# controller.net
KiCad netlist of a schematic drawn in EAGLE
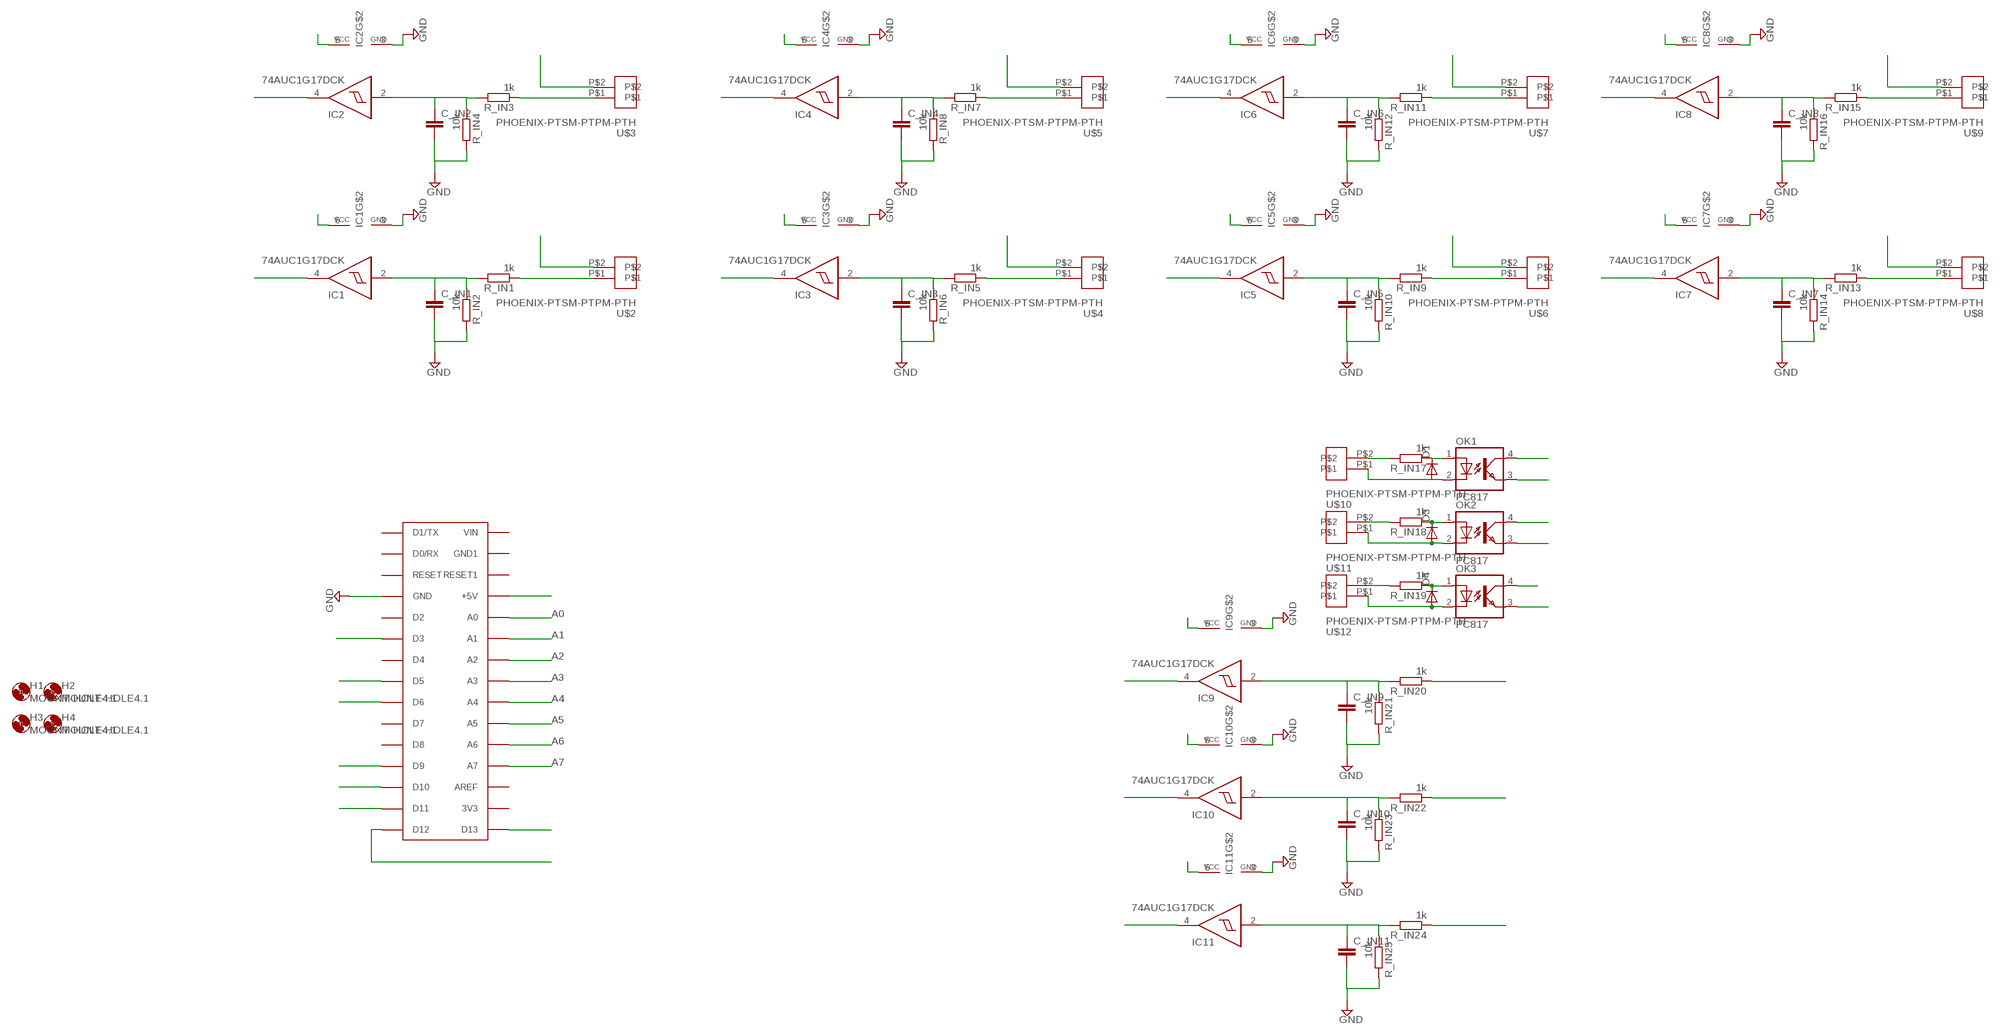
[diagram p0: schematic, sheet 1]

(export (version "E")
  (design (tool "Eeschema 10.0.6"))
  (components
    (comp (ref "C_IN1")
      (value "C-EUC0805")
      (footprint "eagle-import:C0805")
      (libsource (lib "eagle-import") (part "C-EUC0805"))
    )
    (comp (ref "C_IN2")
      (value "C-EUC0805")
      (footprint "eagle-import:C0805")
      (libsource (lib "eagle-import") (part "C-EUC0805"))
    )
    (comp (ref "C_IN3")
      (value "C-EUC0805")
      (footprint "eagle-import:C0805")
      (libsource (lib "eagle-import") (part "C-EUC0805"))
    )
    (comp (ref "C_IN4")
      (value "C-EUC0805")
      (footprint "eagle-import:C0805")
      (libsource (lib "eagle-import") (part "C-EUC0805"))
    )
    (comp (ref "C_IN5")
      (value "C-EUC0805")
      (footprint "eagle-import:C0805")
      (libsource (lib "eagle-import") (part "C-EUC0805"))
    )
    (comp (ref "C_IN6")
      (value "C-EUC0805")
      (footprint "eagle-import:C0805")
      (libsource (lib "eagle-import") (part "C-EUC0805"))
    )
    (comp (ref "C_IN7")
      (value "C-EUC0805")
      (footprint "eagle-import:C0805")
      (libsource (lib "eagle-import") (part "C-EUC0805"))
    )
    (comp (ref "C_IN8")
      (value "C-EUC0805")
      (footprint "eagle-import:C0805")
      (libsource (lib "eagle-import") (part "C-EUC0805"))
    )
    (comp (ref "C_IN9")
      (value "C-EUC0805")
      (footprint "eagle-import:C0805")
      (libsource (lib "eagle-import") (part "C-EUC0805"))
    )
    (comp (ref "C_IN10")
      (value "C-EUC0805")
      (footprint "eagle-import:C0805")
      (libsource (lib "eagle-import") (part "C-EUC0805"))
    )
    (comp (ref "C_IN11")
      (value "C-EUC0805")
      (footprint "eagle-import:C0805")
      (libsource (lib "eagle-import") (part "C-EUC0805"))
    )
    (comp (ref "D1")
      (value "DIODE-DO-214AC")
      (footprint "eagle-import:DO-214AC")
      (libsource (lib "eagle-import") (part "DIODE-DO-214AC"))
    )
    (comp (ref "D3")
      (value "DIODE-DO-214AC")
      (footprint "eagle-import:DO-214AC")
      (libsource (lib "eagle-import") (part "DIODE-DO-214AC"))
    )
    (comp (ref "D4")
      (value "DIODE-DO-214AC")
      (footprint "eagle-import:DO-214AC")
      (libsource (lib "eagle-import") (part "DIODE-DO-214AC"))
    )
    (comp (ref "H1")
      (value "MOUNT-HOLE4.1")
      (footprint "eagle-import:4,1")
      (libsource (lib "eagle-import") (part "MOUNT-HOLE4.1"))
    )
    (comp (ref "H2")
      (value "MOUNT-HOLE4.1")
      (footprint "eagle-import:4,1")
      (libsource (lib "eagle-import") (part "MOUNT-HOLE4.1"))
    )
    (comp (ref "H3")
      (value "MOUNT-HOLE4.1")
      (footprint "eagle-import:4,1")
      (libsource (lib "eagle-import") (part "MOUNT-HOLE4.1"))
    )
    (comp (ref "H4")
      (value "MOUNT-HOLE4.1")
      (footprint "eagle-import:4,1")
      (libsource (lib "eagle-import") (part "MOUNT-HOLE4.1"))
    )
    (comp (ref "IC1")
      (value "74AUC1G17DCK")
      (footprint "eagle-import:SC70-5")
      (libsource (lib "eagle-import") (part "741G17DCKAUC"))
    )
    (comp (ref "IC2")
      (value "74AUC1G17DCK")
      (footprint "eagle-import:SC70-5")
      (libsource (lib "eagle-import") (part "741G17DCKAUC"))
    )
    (comp (ref "IC3")
      (value "74AUC1G17DCK")
      (footprint "eagle-import:SC70-5")
      (libsource (lib "eagle-import") (part "741G17DCKAUC"))
    )
    (comp (ref "IC4")
      (value "74AUC1G17DCK")
      (footprint "eagle-import:SC70-5")
      (libsource (lib "eagle-import") (part "741G17DCKAUC"))
    )
    (comp (ref "IC5")
      (value "74AUC1G17DCK")
      (footprint "eagle-import:SC70-5")
      (libsource (lib "eagle-import") (part "741G17DCKAUC"))
    )
    (comp (ref "IC6")
      (value "74AUC1G17DCK")
      (footprint "eagle-import:SC70-5")
      (libsource (lib "eagle-import") (part "741G17DCKAUC"))
    )
    (comp (ref "IC7")
      (value "74AUC1G17DCK")
      (footprint "eagle-import:SC70-5")
      (libsource (lib "eagle-import") (part "741G17DCKAUC"))
    )
    (comp (ref "IC8")
      (value "74AUC1G17DCK")
      (footprint "eagle-import:SC70-5")
      (libsource (lib "eagle-import") (part "741G17DCKAUC"))
    )
    (comp (ref "IC9")
      (value "74AUC1G17DCK")
      (footprint "eagle-import:SC70-5")
      (libsource (lib "eagle-import") (part "741G17DCKAUC"))
    )
    (comp (ref "IC10")
      (value "74AUC1G17DCK")
      (footprint "eagle-import:SC70-5")
      (libsource (lib "eagle-import") (part "741G17DCKAUC"))
    )
    (comp (ref "IC11")
      (value "74AUC1G17DCK")
      (footprint "eagle-import:SC70-5")
      (libsource (lib "eagle-import") (part "741G17DCKAUC"))
    )
    (comp (ref "OK1")
      (value "PC817")
      (footprint "eagle-import:DIL04")
      (fields (field (name "MPN") "PC817X4J000F"))
      (libsource (lib "eagle-import") (part "PC817"))
    )
    (comp (ref "OK2")
      (value "PC817")
      (footprint "eagle-import:DIL04")
      (fields (field (name "MPN") "PC817X4J000F"))
      (libsource (lib "eagle-import") (part "PC817"))
    )
    (comp (ref "OK3")
      (value "PC817")
      (footprint "eagle-import:DIL04")
      (fields
        (field (name "MPN") "PC817X4J000F")
        (field (name "MPN_1") "PC817X4J000F")
        (field (name "OC_FARNELL") "9707727")
        (field (name "OC_NEWARK") "97K7059")
      )
      (libsource (lib "eagle-import") (part "PC817"))
    )
    (comp (ref "R_IN1")
      (value "1k")
      (footprint "eagle-import:M0805")
      (libsource (lib "eagle-import") (part "R-EU_M0805"))
    )
    (comp (ref "R_IN2")
      (value "10k")
      (footprint "eagle-import:M0805")
      (libsource (lib "eagle-import") (part "R-EU_M0805"))
    )
    (comp (ref "R_IN3")
      (value "1k")
      (footprint "eagle-import:M0805")
      (libsource (lib "eagle-import") (part "R-EU_M0805"))
    )
    (comp (ref "R_IN4")
      (value "10k")
      (footprint "eagle-import:M0805")
      (libsource (lib "eagle-import") (part "R-EU_M0805"))
    )
    (comp (ref "R_IN5")
      (value "1k")
      (footprint "eagle-import:M0805")
      (libsource (lib "eagle-import") (part "R-EU_M0805"))
    )
    (comp (ref "R_IN6")
      (value "10k")
      (footprint "eagle-import:M0805")
      (libsource (lib "eagle-import") (part "R-EU_M0805"))
    )
    (comp (ref "R_IN7")
      (value "1k")
      (footprint "eagle-import:M0805")
      (libsource (lib "eagle-import") (part "R-EU_M0805"))
    )
    (comp (ref "R_IN8")
      (value "10k")
      (footprint "eagle-import:M0805")
      (libsource (lib "eagle-import") (part "R-EU_M0805"))
    )
    (comp (ref "R_IN9")
      (value "1k")
      (footprint "eagle-import:M0805")
      (libsource (lib "eagle-import") (part "R-EU_M0805"))
    )
    (comp (ref "R_IN10")
      (value "10k")
      (footprint "eagle-import:M0805")
      (libsource (lib "eagle-import") (part "R-EU_M0805"))
    )
    (comp (ref "R_IN11")
      (value "1k")
      (footprint "eagle-import:M0805")
      (libsource (lib "eagle-import") (part "R-EU_M0805"))
    )
    (comp (ref "R_IN12")
      (value "10k")
      (footprint "eagle-import:M0805")
      (libsource (lib "eagle-import") (part "R-EU_M0805"))
    )
    (comp (ref "R_IN13")
      (value "1k")
      (footprint "eagle-import:M0805")
      (libsource (lib "eagle-import") (part "R-EU_M0805"))
    )
    (comp (ref "R_IN14")
      (value "10k")
      (footprint "eagle-import:M0805")
      (libsource (lib "eagle-import") (part "R-EU_M0805"))
    )
    (comp (ref "R_IN15")
      (value "1k")
      (footprint "eagle-import:M0805")
      (libsource (lib "eagle-import") (part "R-EU_M0805"))
    )
    (comp (ref "R_IN16")
      (value "10k")
      (footprint "eagle-import:M0805")
      (libsource (lib "eagle-import") (part "R-EU_M0805"))
    )
    (comp (ref "R_IN17")
      (value "1k")
      (footprint "eagle-import:M1206")
      (libsource (lib "eagle-import") (part "R-EU_M1206"))
    )
    (comp (ref "R_IN18")
      (value "1k")
      (footprint "eagle-import:M1206")
      (libsource (lib "eagle-import") (part "R-EU_M1206"))
    )
    (comp (ref "R_IN19")
      (value "1k")
      (footprint "eagle-import:M1206")
      (libsource (lib "eagle-import") (part "R-EU_M1206"))
    )
    (comp (ref "R_IN20")
      (value "1k")
      (footprint "eagle-import:M0805")
      (libsource (lib "eagle-import") (part "R-EU_M0805"))
    )
    (comp (ref "R_IN21")
      (value "10k")
      (footprint "eagle-import:M0805")
      (libsource (lib "eagle-import") (part "R-EU_M0805"))
    )
    (comp (ref "R_IN22")
      (value "1k")
      (footprint "eagle-import:M0805")
      (libsource (lib "eagle-import") (part "R-EU_M0805"))
    )
    (comp (ref "R_IN23")
      (value "10k")
      (footprint "eagle-import:M0805")
      (libsource (lib "eagle-import") (part "R-EU_M0805"))
    )
    (comp (ref "R_IN24")
      (value "1k")
      (footprint "eagle-import:M0805")
      (libsource (lib "eagle-import") (part "R-EU_M0805"))
    )
    (comp (ref "R_IN25")
      (value "10k")
      (footprint "eagle-import:M0805")
      (libsource (lib "eagle-import") (part "R-EU_M0805"))
    )
    (comp (ref "U$1")
      (value "ARDUINONANO")
      (footprint "eagle-import:PDIP-32")
      (libsource (lib "eagle-import") (part "ARDUINONANO"))
    )
    (comp (ref "U$2")
      (value "PHOENIX-PTSM-PTPM-PTH")
      (footprint "eagle-import:PTSM-PTH-2.5MM-2")
      (libsource (lib "eagle-import") (part "PHOENIX-PTSM-PTPM-PTH"))
    )
    (comp (ref "U$3")
      (value "PHOENIX-PTSM-PTPM-PTH")
      (footprint "eagle-import:PTSM-PTH-2.5MM-2")
      (libsource (lib "eagle-import") (part "PHOENIX-PTSM-PTPM-PTH"))
    )
    (comp (ref "U$4")
      (value "PHOENIX-PTSM-PTPM-PTH")
      (footprint "eagle-import:PTSM-PTH-2.5MM-2")
      (libsource (lib "eagle-import") (part "PHOENIX-PTSM-PTPM-PTH"))
    )
    (comp (ref "U$5")
      (value "PHOENIX-PTSM-PTPM-PTH")
      (footprint "eagle-import:PTSM-PTH-2.5MM-2")
      (libsource (lib "eagle-import") (part "PHOENIX-PTSM-PTPM-PTH"))
    )
    (comp (ref "U$6")
      (value "PHOENIX-PTSM-PTPM-PTH")
      (footprint "eagle-import:PTSM-PTH-2.5MM-2")
      (libsource (lib "eagle-import") (part "PHOENIX-PTSM-PTPM-PTH"))
    )
    (comp (ref "U$7")
      (value "PHOENIX-PTSM-PTPM-PTH")
      (footprint "eagle-import:PTSM-PTH-2.5MM-2")
      (libsource (lib "eagle-import") (part "PHOENIX-PTSM-PTPM-PTH"))
    )
    (comp (ref "U$8")
      (value "PHOENIX-PTSM-PTPM-PTH")
      (footprint "eagle-import:PTSM-PTH-2.5MM-2")
      (libsource (lib "eagle-import") (part "PHOENIX-PTSM-PTPM-PTH"))
    )
    (comp (ref "U$9")
      (value "PHOENIX-PTSM-PTPM-PTH")
      (footprint "eagle-import:PTSM-PTH-2.5MM-2")
      (libsource (lib "eagle-import") (part "PHOENIX-PTSM-PTPM-PTH"))
    )
    (comp (ref "U$10")
      (value "PHOENIX-PTSM-PTPM-PTH")
      (footprint "eagle-import:PTSM-PTH-2.5MM-2")
      (libsource (lib "eagle-import") (part "PHOENIX-PTSM-PTPM-PTH"))
    )
    (comp (ref "U$11")
      (value "PHOENIX-PTSM-PTPM-PTH")
      (footprint "eagle-import:PTSM-PTH-2.5MM-2")
      (libsource (lib "eagle-import") (part "PHOENIX-PTSM-PTPM-PTH"))
    )
    (comp (ref "U$12")
      (value "PHOENIX-PTSM-PTPM-PTH")
      (footprint "eagle-import:PTSM-PTH-2.5MM-2")
      (libsource (lib "eagle-import") (part "PHOENIX-PTSM-PTPM-PTH"))
    )
  )
  (nets
    (net (code "1") (name "/+5V") (class "Default")
      (node (ref "IC1") (pin "5") (pinfunction "VCC_5") (pintype "power_in"))
      (node (ref "IC2") (pin "5") (pinfunction "VCC_5") (pintype "power_in"))
      (node (ref "IC3") (pin "5") (pinfunction "VCC_5") (pintype "power_in"))
      (node (ref "IC4") (pin "5") (pinfunction "VCC_5") (pintype "power_in"))
      (node (ref "IC5") (pin "5") (pinfunction "VCC_5") (pintype "power_in"))
      (node (ref "IC6") (pin "5") (pinfunction "VCC_5") (pintype "power_in"))
      (node (ref "IC7") (pin "5") (pinfunction "VCC_5") (pintype "power_in"))
      (node (ref "IC8") (pin "5") (pinfunction "VCC_5") (pintype "power_in"))
      (node (ref "OK1") (pin "4") (pinfunction "COL_4") (pintype "passive"))
      (node (ref "OK2") (pin "4") (pinfunction "COL_4") (pintype "passive"))
      (node (ref "OK3") (pin "4") (pinfunction "COL_4") (pintype "passive"))
      (node (ref "U$1") (pin "+5V") (pinfunction "+5V_+5V") (pintype "bidirectional"))
      (node (ref "U$2") (pin "P$2") (pinfunction "P$2_P$2") (pintype "bidirectional"))
      (node (ref "U$3") (pin "P$2") (pinfunction "P$2_P$2") (pintype "bidirectional"))
      (node (ref "U$4") (pin "P$2") (pinfunction "P$2_P$2") (pintype "bidirectional"))
      (node (ref "U$5") (pin "P$2") (pinfunction "P$2_P$2") (pintype "bidirectional"))
      (node (ref "U$6") (pin "P$2") (pinfunction "P$2_P$2") (pintype "bidirectional"))
      (node (ref "U$7") (pin "P$2") (pinfunction "P$2_P$2") (pintype "bidirectional"))
      (node (ref "U$8") (pin "P$2") (pinfunction "P$2_P$2") (pintype "bidirectional"))
      (node (ref "U$9") (pin "P$2") (pinfunction "P$2_P$2") (pintype "bidirectional"))
    )
    (net (code "2") (name "/A0") (class "Default")
      (node (ref "IC1") (pin "4") (pinfunction "O_4") (pintype "output"))
      (node (ref "U$1") (pin "A0") (pinfunction "A0_A0") (pintype "bidirectional"))
    )
    (net (code "3") (name "/A1") (class "Default")
      (node (ref "IC2") (pin "4") (pinfunction "O_4") (pintype "output"))
      (node (ref "U$1") (pin "A1") (pinfunction "A1_A1") (pintype "bidirectional"))
    )
    (net (code "4") (name "/A2") (class "Default")
      (node (ref "IC3") (pin "4") (pinfunction "O_4") (pintype "output"))
      (node (ref "U$1") (pin "A2") (pinfunction "A2_A2") (pintype "bidirectional"))
    )
    (net (code "5") (name "/A3") (class "Default")
      (node (ref "IC4") (pin "4") (pinfunction "O_4") (pintype "output"))
      (node (ref "U$1") (pin "A3") (pinfunction "A3_A3") (pintype "bidirectional"))
    )
    (net (code "6") (name "/A4") (class "Default")
      (node (ref "IC5") (pin "4") (pinfunction "O_4") (pintype "output"))
      (node (ref "U$1") (pin "A4") (pinfunction "A4_A4") (pintype "bidirectional"))
    )
    (net (code "7") (name "/A5") (class "Default")
      (node (ref "IC6") (pin "4") (pinfunction "O_4") (pintype "output"))
      (node (ref "U$1") (pin "A5") (pinfunction "A5_A5") (pintype "bidirectional"))
    )
    (net (code "8") (name "/A6") (class "Default")
      (node (ref "IC7") (pin "4") (pinfunction "O_4") (pintype "output"))
      (node (ref "U$1") (pin "A6") (pinfunction "A6_A6") (pintype "bidirectional"))
    )
    (net (code "9") (name "/A7") (class "Default")
      (node (ref "IC8") (pin "4") (pinfunction "O_4") (pintype "output"))
      (node (ref "U$1") (pin "A7") (pinfunction "A7_A7") (pintype "bidirectional"))
    )
    (net (code "10") (name "/N$21") (class "Default")
      (node (ref "OK1") (pin "3") (pinfunction "EMIT_3") (pintype "passive"))
      (node (ref "R_IN20") (pin "1") (pinfunction "1_1") (pintype "passive"))
    )
    (net (code "11") (name "/N$22") (class "Default")
      (node (ref "OK2") (pin "3") (pinfunction "EMIT_3") (pintype "passive"))
      (node (ref "R_IN22") (pin "1") (pinfunction "1_1") (pintype "passive"))
    )
    (net (code "12") (name "/N$23") (class "Default")
      (node (ref "OK3") (pin "3") (pinfunction "EMIT_3") (pintype "passive"))
      (node (ref "R_IN24") (pin "1") (pinfunction "1_1") (pintype "passive"))
    )
    (net (code "13") (name "GND") (class "Default")
      (node (ref "C_IN1") (pin "2") (pinfunction "2_2") (pintype "passive"))
      (node (ref "C_IN10") (pin "2") (pinfunction "2_2") (pintype "passive"))
      (node (ref "C_IN11") (pin "2") (pinfunction "2_2") (pintype "passive"))
      (node (ref "C_IN2") (pin "2") (pinfunction "2_2") (pintype "passive"))
      (node (ref "C_IN3") (pin "2") (pinfunction "2_2") (pintype "passive"))
      (node (ref "C_IN4") (pin "2") (pinfunction "2_2") (pintype "passive"))
      (node (ref "C_IN5") (pin "2") (pinfunction "2_2") (pintype "passive"))
      (node (ref "C_IN6") (pin "2") (pinfunction "2_2") (pintype "passive"))
      (node (ref "C_IN7") (pin "2") (pinfunction "2_2") (pintype "passive"))
      (node (ref "C_IN8") (pin "2") (pinfunction "2_2") (pintype "passive"))
      (node (ref "C_IN9") (pin "2") (pinfunction "2_2") (pintype "passive"))
      (node (ref "IC1") (pin "3") (pinfunction "GND_3") (pintype "power_in"))
      (node (ref "IC10") (pin "3") (pinfunction "GND_3") (pintype "power_in"))
      (node (ref "IC11") (pin "3") (pinfunction "GND_3") (pintype "power_in"))
      (node (ref "IC2") (pin "3") (pinfunction "GND_3") (pintype "power_in"))
      (node (ref "IC3") (pin "3") (pinfunction "GND_3") (pintype "power_in"))
      (node (ref "IC4") (pin "3") (pinfunction "GND_3") (pintype "power_in"))
      (node (ref "IC5") (pin "3") (pinfunction "GND_3") (pintype "power_in"))
      (node (ref "IC6") (pin "3") (pinfunction "GND_3") (pintype "power_in"))
      (node (ref "IC7") (pin "3") (pinfunction "GND_3") (pintype "power_in"))
      (node (ref "IC8") (pin "3") (pinfunction "GND_3") (pintype "power_in"))
      (node (ref "IC9") (pin "3") (pinfunction "GND_3") (pintype "power_in"))
      (node (ref "R_IN10") (pin "2") (pinfunction "2_2") (pintype "passive"))
      (node (ref "R_IN12") (pin "2") (pinfunction "2_2") (pintype "passive"))
      (node (ref "R_IN14") (pin "2") (pinfunction "2_2") (pintype "passive"))
      (node (ref "R_IN16") (pin "2") (pinfunction "2_2") (pintype "passive"))
      (node (ref "R_IN2") (pin "2") (pinfunction "2_2") (pintype "passive"))
      (node (ref "R_IN21") (pin "2") (pinfunction "2_2") (pintype "passive"))
      (node (ref "R_IN23") (pin "2") (pinfunction "2_2") (pintype "passive"))
      (node (ref "R_IN25") (pin "2") (pinfunction "2_2") (pintype "passive"))
      (node (ref "R_IN4") (pin "2") (pinfunction "2_2") (pintype "passive"))
      (node (ref "R_IN6") (pin "2") (pinfunction "2_2") (pintype "passive"))
      (node (ref "R_IN8") (pin "2") (pinfunction "2_2") (pintype "passive"))
      (node (ref "U$1") (pin "GND") (pinfunction "GND_GND") (pintype "bidirectional"))
    )
    (net (code "14") (name "Net-(IC1A-I)") (class "Default")
      (node (ref "C_IN1") (pin "1") (pinfunction "1_1") (pintype "passive"))
      (node (ref "IC1") (pin "2") (pinfunction "I_2") (pintype "input"))
      (node (ref "R_IN1") (pin "2") (pinfunction "2_2") (pintype "passive"))
      (node (ref "R_IN2") (pin "1") (pinfunction "1_1") (pintype "passive"))
    )
    (net (code "15") (name "Net-(IC2A-I)") (class "Default")
      (node (ref "C_IN2") (pin "1") (pinfunction "1_1") (pintype "passive"))
      (node (ref "IC2") (pin "2") (pinfunction "I_2") (pintype "input"))
      (node (ref "R_IN3") (pin "2") (pinfunction "2_2") (pintype "passive"))
      (node (ref "R_IN4") (pin "1") (pinfunction "1_1") (pintype "passive"))
    )
    (net (code "16") (name "Net-(IC3A-I)") (class "Default")
      (node (ref "C_IN3") (pin "1") (pinfunction "1_1") (pintype "passive"))
      (node (ref "IC3") (pin "2") (pinfunction "I_2") (pintype "input"))
      (node (ref "R_IN5") (pin "2") (pinfunction "2_2") (pintype "passive"))
      (node (ref "R_IN6") (pin "1") (pinfunction "1_1") (pintype "passive"))
    )
    (net (code "17") (name "Net-(IC4A-I)") (class "Default")
      (node (ref "C_IN4") (pin "1") (pinfunction "1_1") (pintype "passive"))
      (node (ref "IC4") (pin "2") (pinfunction "I_2") (pintype "input"))
      (node (ref "R_IN7") (pin "2") (pinfunction "2_2") (pintype "passive"))
      (node (ref "R_IN8") (pin "1") (pinfunction "1_1") (pintype "passive"))
    )
    (net (code "18") (name "Net-(IC5A-I)") (class "Default")
      (node (ref "C_IN5") (pin "1") (pinfunction "1_1") (pintype "passive"))
      (node (ref "IC5") (pin "2") (pinfunction "I_2") (pintype "input"))
      (node (ref "R_IN10") (pin "1") (pinfunction "1_1") (pintype "passive"))
      (node (ref "R_IN9") (pin "2") (pinfunction "2_2") (pintype "passive"))
    )
    (net (code "19") (name "Net-(IC6A-I)") (class "Default")
      (node (ref "C_IN6") (pin "1") (pinfunction "1_1") (pintype "passive"))
      (node (ref "IC6") (pin "2") (pinfunction "I_2") (pintype "input"))
      (node (ref "R_IN11") (pin "2") (pinfunction "2_2") (pintype "passive"))
      (node (ref "R_IN12") (pin "1") (pinfunction "1_1") (pintype "passive"))
    )
    (net (code "20") (name "Net-(IC7A-I)") (class "Default")
      (node (ref "C_IN7") (pin "1") (pinfunction "1_1") (pintype "passive"))
      (node (ref "IC7") (pin "2") (pinfunction "I_2") (pintype "input"))
      (node (ref "R_IN13") (pin "2") (pinfunction "2_2") (pintype "passive"))
      (node (ref "R_IN14") (pin "1") (pinfunction "1_1") (pintype "passive"))
    )
    (net (code "21") (name "Net-(IC8A-I)") (class "Default")
      (node (ref "C_IN8") (pin "1") (pinfunction "1_1") (pintype "passive"))
      (node (ref "IC8") (pin "2") (pinfunction "I_2") (pintype "input"))
      (node (ref "R_IN15") (pin "2") (pinfunction "2_2") (pintype "passive"))
      (node (ref "R_IN16") (pin "1") (pinfunction "1_1") (pintype "passive"))
    )
    (net (code "22") (name "Net-(IC9A-I)") (class "Default")
      (node (ref "C_IN9") (pin "1") (pinfunction "1_1") (pintype "passive"))
      (node (ref "IC9") (pin "2") (pinfunction "I_2") (pintype "input"))
      (node (ref "R_IN20") (pin "2") (pinfunction "2_2") (pintype "passive"))
      (node (ref "R_IN21") (pin "1") (pinfunction "1_1") (pintype "passive"))
    )
    (net (code "23") (name "Net-(IC10A-I)") (class "Default")
      (node (ref "C_IN10") (pin "1") (pinfunction "1_1") (pintype "passive"))
      (node (ref "IC10") (pin "2") (pinfunction "I_2") (pintype "input"))
      (node (ref "R_IN22") (pin "2") (pinfunction "2_2") (pintype "passive"))
      (node (ref "R_IN23") (pin "1") (pinfunction "1_1") (pintype "passive"))
    )
    (net (code "24") (name "Net-(IC11A-I)") (class "Default")
      (node (ref "C_IN11") (pin "1") (pinfunction "1_1") (pintype "passive"))
      (node (ref "IC11") (pin "2") (pinfunction "I_2") (pintype "input"))
      (node (ref "R_IN24") (pin "2") (pinfunction "2_2") (pintype "passive"))
      (node (ref "R_IN25") (pin "1") (pinfunction "1_1") (pintype "passive"))
    )
    (net (code "25") (name "Net-(OK1-A)") (class "Default")
      (node (ref "D1") (pin "C") (pinfunction "C_C") (pintype "passive"))
      (node (ref "OK1") (pin "1") (pinfunction "A_1") (pintype "passive"))
      (node (ref "R_IN17") (pin "1") (pinfunction "1_1") (pintype "passive"))
    )
    (net (code "26") (name "Net-(OK1-C)") (class "Default")
      (node (ref "D1") (pin "A") (pinfunction "A_A") (pintype "passive"))
      (node (ref "OK1") (pin "2") (pinfunction "C_2") (pintype "passive"))
      (node (ref "U$10") (pin "P$1") (pinfunction "P$1_P$1") (pintype "bidirectional"))
    )
    (net (code "27") (name "Net-(OK2-A)") (class "Default")
      (node (ref "D3") (pin "C") (pinfunction "C_C") (pintype "passive"))
      (node (ref "OK2") (pin "1") (pinfunction "A_1") (pintype "passive"))
      (node (ref "R_IN18") (pin "1") (pinfunction "1_1") (pintype "passive"))
    )
    (net (code "28") (name "Net-(OK2-C)") (class "Default")
      (node (ref "D3") (pin "A") (pinfunction "A_A") (pintype "passive"))
      (node (ref "OK2") (pin "2") (pinfunction "C_2") (pintype "passive"))
      (node (ref "U$11") (pin "P$1") (pinfunction "P$1_P$1") (pintype "bidirectional"))
    )
    (net (code "29") (name "Net-(OK3-A)") (class "Default")
      (node (ref "D4") (pin "C") (pinfunction "C_C") (pintype "passive"))
      (node (ref "OK3") (pin "1") (pinfunction "A_1") (pintype "passive"))
      (node (ref "R_IN19") (pin "1") (pinfunction "1_1") (pintype "passive"))
    )
    (net (code "30") (name "Net-(OK3-C)") (class "Default")
      (node (ref "D4") (pin "A") (pinfunction "A_A") (pintype "passive"))
      (node (ref "OK3") (pin "2") (pinfunction "C_2") (pintype "passive"))
      (node (ref "U$12") (pin "P$1") (pinfunction "P$1_P$1") (pintype "bidirectional"))
    )
    (net (code "31") (name "Net-(R_IN1-Pad1)") (class "Default")
      (node (ref "R_IN1") (pin "1") (pinfunction "1_1") (pintype "passive"))
      (node (ref "U$2") (pin "P$1") (pinfunction "P$1_P$1") (pintype "bidirectional"))
    )
    (net (code "32") (name "Net-(R_IN3-Pad1)") (class "Default")
      (node (ref "R_IN3") (pin "1") (pinfunction "1_1") (pintype "passive"))
      (node (ref "U$3") (pin "P$1") (pinfunction "P$1_P$1") (pintype "bidirectional"))
    )
    (net (code "33") (name "Net-(R_IN5-Pad1)") (class "Default")
      (node (ref "R_IN5") (pin "1") (pinfunction "1_1") (pintype "passive"))
      (node (ref "U$4") (pin "P$1") (pinfunction "P$1_P$1") (pintype "bidirectional"))
    )
    (net (code "34") (name "Net-(R_IN7-Pad1)") (class "Default")
      (node (ref "R_IN7") (pin "1") (pinfunction "1_1") (pintype "passive"))
      (node (ref "U$5") (pin "P$1") (pinfunction "P$1_P$1") (pintype "bidirectional"))
    )
    (net (code "35") (name "Net-(R_IN9-Pad1)") (class "Default")
      (node (ref "R_IN9") (pin "1") (pinfunction "1_1") (pintype "passive"))
      (node (ref "U$6") (pin "P$1") (pinfunction "P$1_P$1") (pintype "bidirectional"))
    )
    (net (code "36") (name "Net-(R_IN11-Pad1)") (class "Default")
      (node (ref "R_IN11") (pin "1") (pinfunction "1_1") (pintype "passive"))
      (node (ref "U$7") (pin "P$1") (pinfunction "P$1_P$1") (pintype "bidirectional"))
    )
    (net (code "37") (name "Net-(R_IN13-Pad1)") (class "Default")
      (node (ref "R_IN13") (pin "1") (pinfunction "1_1") (pintype "passive"))
      (node (ref "U$8") (pin "P$1") (pinfunction "P$1_P$1") (pintype "bidirectional"))
    )
    (net (code "38") (name "Net-(R_IN15-Pad1)") (class "Default")
      (node (ref "R_IN15") (pin "1") (pinfunction "1_1") (pintype "passive"))
      (node (ref "U$9") (pin "P$1") (pinfunction "P$1_P$1") (pintype "bidirectional"))
    )
    (net (code "39") (name "Net-(R_IN17-Pad2)") (class "Default")
      (node (ref "R_IN17") (pin "2") (pinfunction "2_2") (pintype "passive"))
      (node (ref "U$10") (pin "P$2") (pinfunction "P$2_P$2") (pintype "bidirectional"))
    )
    (net (code "40") (name "Net-(R_IN18-Pad2)") (class "Default")
      (node (ref "R_IN18") (pin "2") (pinfunction "2_2") (pintype "passive"))
      (node (ref "U$11") (pin "P$2") (pinfunction "P$2_P$2") (pintype "bidirectional"))
    )
    (net (code "41") (name "Net-(R_IN19-Pad2)") (class "Default")
      (node (ref "R_IN19") (pin "2") (pinfunction "2_2") (pintype "passive"))
      (node (ref "U$12") (pin "P$2") (pinfunction "P$2_P$2") (pintype "bidirectional"))
    )
    (net (code "42") (name "unconnected-(IC9A-O-Pad4)") (class "Default")
      (node (ref "IC9") (pin "4") (pinfunction "O_4") (pintype "output"))
    )
    (net (code "43") (name "unconnected-(IC9B-VCC-Pad5)") (class "Default")
      (node (ref "IC9") (pin "5") (pinfunction "VCC_5") (pintype "power_in"))
    )
    (net (code "44") (name "unconnected-(IC10A-O-Pad4)") (class "Default")
      (node (ref "IC10") (pin "4") (pinfunction "O_4") (pintype "output"))
    )
    (net (code "45") (name "unconnected-(IC10B-VCC-Pad5)") (class "Default")
      (node (ref "IC10") (pin "5") (pinfunction "VCC_5") (pintype "power_in"))
    )
    (net (code "46") (name "unconnected-(IC11A-O-Pad4)") (class "Default")
      (node (ref "IC11") (pin "4") (pinfunction "O_4") (pintype "output"))
    )
    (net (code "47") (name "unconnected-(IC11B-VCC-Pad5)") (class "Default")
      (node (ref "IC11") (pin "5") (pinfunction "VCC_5") (pintype "power_in"))
    )
    (net (code "48") (name "unconnected-(U$1-Pad3V3)") (class "Default")
      (node (ref "U$1") (pin "3V3") (pinfunction "3V3_3V3") (pintype "bidirectional"))
    )
    (net (code "49") (name "unconnected-(U$1-PadAREF)") (class "Default")
      (node (ref "U$1") (pin "AREF") (pinfunction "AREF_AREF") (pintype "bidirectional"))
    )
    (net (code "50") (name "unconnected-(U$1-PadD0{slash}RX)") (class "Default")
      (node (ref "U$1") (pin "D0/RX") (pinfunction "D0/RX_D0/RX") (pintype "bidirectional"))
    )
    (net (code "51") (name "unconnected-(U$1-PadD1{slash}TX)") (class "Default")
      (node (ref "U$1") (pin "D1/TX") (pinfunction "D1/TX_D1/TX") (pintype "bidirectional"))
    )
    (net (code "52") (name "unconnected-(U$1-PadD2)") (class "Default")
      (node (ref "U$1") (pin "D2") (pinfunction "D2_D2") (pintype "bidirectional"))
    )
    (net (code "53") (name "unconnected-(U$1-PadD3)") (class "Default")
      (node (ref "U$1") (pin "D3") (pinfunction "D3_D3") (pintype "bidirectional"))
    )
    (net (code "54") (name "unconnected-(U$1-PadD4)") (class "Default")
      (node (ref "U$1") (pin "D4") (pinfunction "D4_D4") (pintype "bidirectional"))
    )
    (net (code "55") (name "unconnected-(U$1-PadD5)") (class "Default")
      (node (ref "U$1") (pin "D5") (pinfunction "D5_D5") (pintype "bidirectional"))
    )
    (net (code "56") (name "unconnected-(U$1-PadD6)") (class "Default")
      (node (ref "U$1") (pin "D6") (pinfunction "D6_D6") (pintype "bidirectional"))
    )
    (net (code "57") (name "unconnected-(U$1-PadD7)") (class "Default")
      (node (ref "U$1") (pin "D7") (pinfunction "D7_D7") (pintype "bidirectional"))
    )
    (net (code "58") (name "unconnected-(U$1-PadD8)") (class "Default")
      (node (ref "U$1") (pin "D8") (pinfunction "D8_D8") (pintype "bidirectional"))
    )
    (net (code "59") (name "unconnected-(U$1-PadD9)") (class "Default")
      (node (ref "U$1") (pin "D9") (pinfunction "D9_D9") (pintype "bidirectional"))
    )
    (net (code "60") (name "unconnected-(U$1-PadD10)") (class "Default")
      (node (ref "U$1") (pin "D10") (pinfunction "D10_D10") (pintype "bidirectional"))
    )
    (net (code "61") (name "unconnected-(U$1-PadD11)") (class "Default")
      (node (ref "U$1") (pin "D11") (pinfunction "D11_D11") (pintype "bidirectional"))
    )
    (net (code "62") (name "unconnected-(U$1-PadD12)") (class "Default")
      (node (ref "U$1") (pin "D12") (pinfunction "D12_D12") (pintype "bidirectional"))
    )
    (net (code "63") (name "unconnected-(U$1-PadD13)") (class "Default")
      (node (ref "U$1") (pin "D13") (pinfunction "D13_D13") (pintype "bidirectional"))
    )
    (net (code "64") (name "unconnected-(U$1-PadGND1)") (class "Default")
      (node (ref "U$1") (pin "GND1") (pinfunction "GND1_GND1") (pintype "bidirectional"))
    )
    (net (code "65") (name "unconnected-(U$1-PadRESET)") (class "Default")
      (node (ref "U$1") (pin "RESET") (pinfunction "RESET_RESET") (pintype "bidirectional"))
    )
    (net (code "66") (name "unconnected-(U$1-PadRESET1)") (class "Default")
      (node (ref "U$1") (pin "RESET1") (pinfunction "RESET1_RESET1") (pintype "bidirectional"))
    )
    (net (code "67") (name "unconnected-(U$1-PadVIN)") (class "Default")
      (node (ref "U$1") (pin "VIN") (pinfunction "VIN_VIN") (pintype "bidirectional"))
    )
  )
)
